# 808_bass_drum1.net
KiCad netlist of a schematic drawn in EAGLE
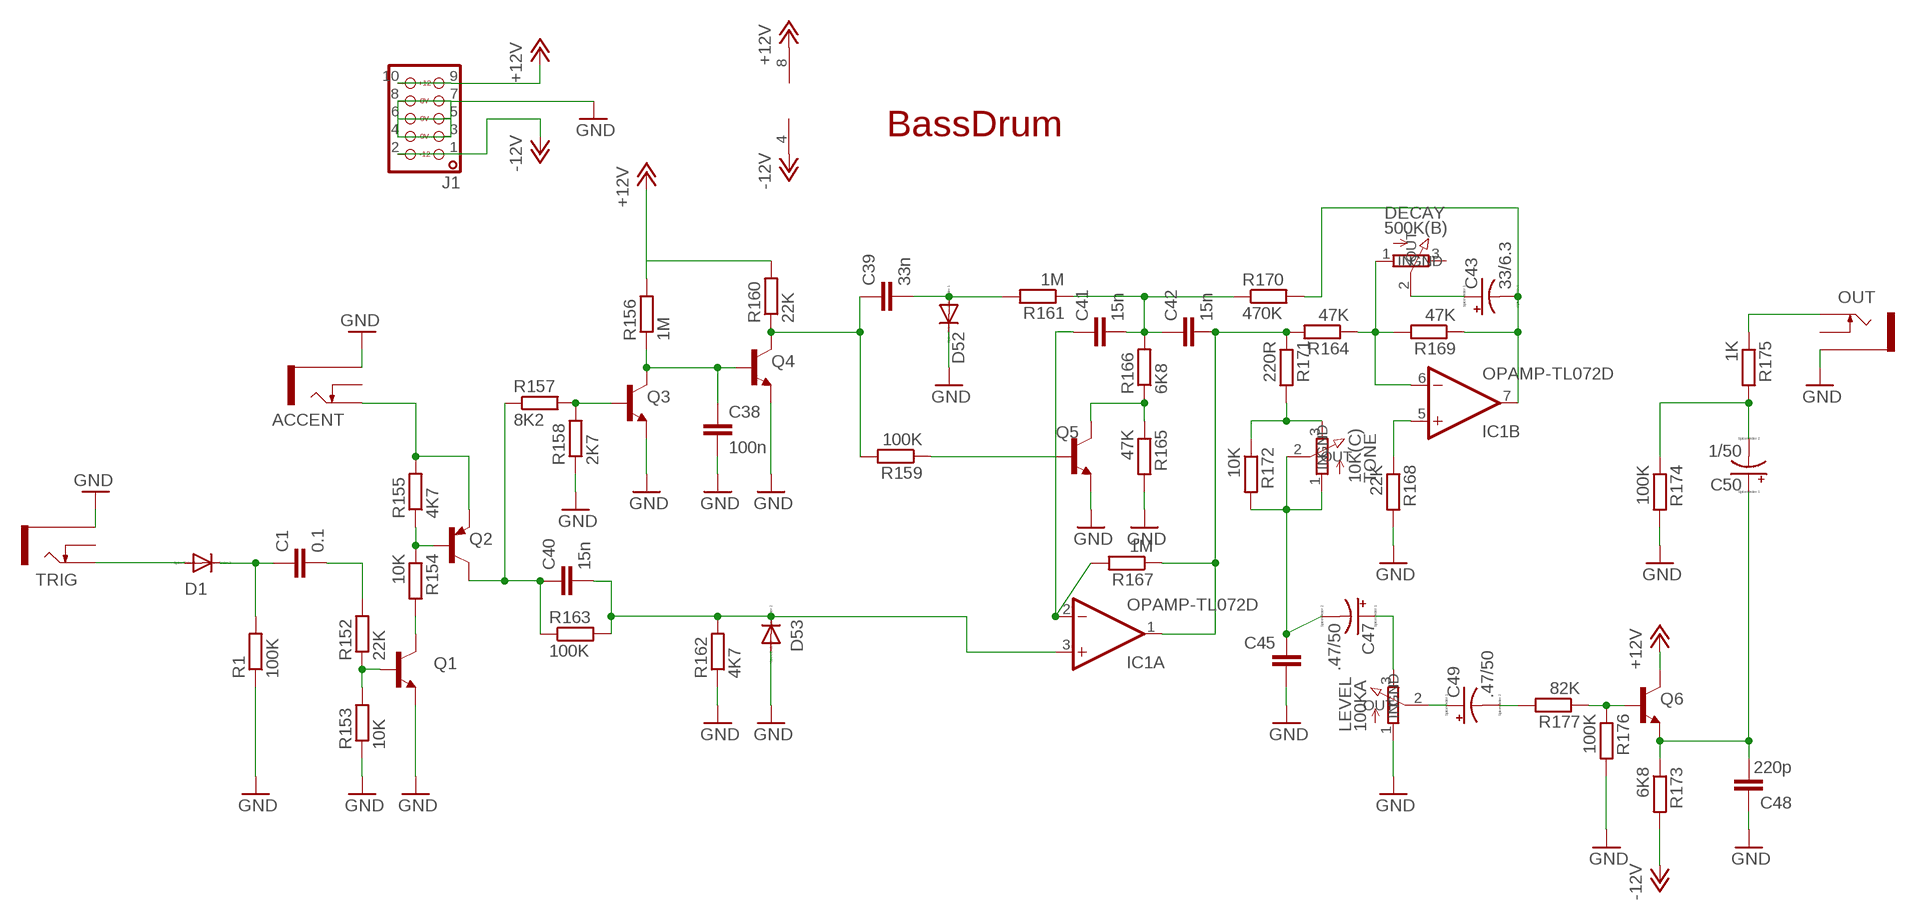
[diagram p0: schematic, sheet 1]

(export (version "E")
  (design (tool "Eeschema 10.0.6"))
  (components
    (comp (ref "ACCENT")
      (value "JACK_THONKICONNNEW")
      (footprint "eagle-import:WQP-PJ301M-12_JACK")
      (libsource (lib "eagle-import") (part "JACK_THONKICONNNEW"))
    )
    (comp (ref "C1")
      (value "0.1")
      (footprint "eagle-import:C0603")
      (libsource (lib "eagle-import") (part "CAPACITOR-EUC0603"))
    )
    (comp (ref "C38")
      (value "100n")
      (footprint "eagle-import:C0603")
      (libsource (lib "eagle-import") (part "CAPACITOR-EUC0603"))
    )
    (comp (ref "C39")
      (value "33n")
      (footprint "eagle-import:C0603")
      (libsource (lib "eagle-import") (part "CAPACITOR-EUC0603"))
    )
    (comp (ref "C40")
      (value "15n")
      (footprint "eagle-import:C0603")
      (libsource (lib "eagle-import") (part "CAPACITOR-EUC0603"))
    )
    (comp (ref "C41")
      (value "15n")
      (footprint "eagle-import:C0603")
      (libsource (lib "eagle-import") (part "CAPACITOR-EUC0603"))
    )
    (comp (ref "C42")
      (value "15n")
      (footprint "eagle-import:C0603")
      (libsource (lib "eagle-import") (part "CAPACITOR-EUC0603"))
    )
    (comp (ref "C43")
      (value "33/6.3")
      (footprint "eagle-import:E2,5-5")
      (libsource (lib "eagle-import") (part "CAPACITOR_POLARIZED-USE2.5-5"))
    )
    (comp (ref "C45")
      (value "100n")
      (footprint "eagle-import:C0603")
      (libsource (lib "eagle-import") (part "CAPACITOR-EUC0603"))
    )
    (comp (ref "C47")
      (value ".47/50")
      (footprint "eagle-import:E2,5-5")
      (libsource (lib "eagle-import") (part "CAPACITOR_POLARIZED-USE2.5-5"))
    )
    (comp (ref "C48")
      (value "220p")
      (footprint "eagle-import:C0603")
      (libsource (lib "eagle-import") (part "CAPACITOR-EUC0603"))
    )
    (comp (ref "C49")
      (value ".47/50")
      (footprint "eagle-import:E2,5-5")
      (libsource (lib "eagle-import") (part "CAPACITOR_POLARIZED-USE2.5-5"))
    )
    (comp (ref "C50")
      (value "1/50")
      (footprint "eagle-import:E2,5-5")
      (libsource (lib "eagle-import") (part "CAPACITOR_POLARIZED-USE2.5-5"))
    )
    (comp (ref "D1")
      (value "1N4148")
      (footprint "eagle-import:SOD323W_INFINEON")
      (libsource (lib "eagle-import") (part "DIODE-1N4148SOD-323"))
    )
    (comp (ref "D52")
      (value "1N4148")
      (footprint "eagle-import:SOD323W_INFINEON")
      (libsource (lib "eagle-import") (part "DIODE-1N4148SOD-323"))
    )
    (comp (ref "D53")
      (value "1N4148")
      (footprint "eagle-import:SOD323W_INFINEON")
      (libsource (lib "eagle-import") (part "DIODE-1N4148SOD-323"))
    )
    (comp (ref "DECAY")
      (value "500K(B)")
      (footprint "eagle-import:9MM_PLS")
      (libsource (lib "eagle-import") (part "POT_9MM_PCB-PLS"))
    )
    (comp (ref "IC1")
      (value "OPAMP-TL072D")
      (footprint "eagle-import:SO08")
      (libsource (lib "eagle-import") (part "OPAMP-TL072D"))
    )
    (comp (ref "J1")
      (value "HEADER-EUROPWR_2X05-OPEN")
      (footprint "eagle-import:2X05_EUROPWR_OPEN")
      (libsource (lib "eagle-import") (part "HEADER-EUROPWR_2X05-OPEN"))
    )
    (comp (ref "LEVEL")
      (value "100KA")
      (footprint "eagle-import:9MM_PLS")
      (libsource (lib "eagle-import") (part "POT_9MM_PCB-PLS"))
    )
    (comp (ref "OUT")
      (value "JACK_THONKICONNNEW")
      (footprint "eagle-import:WQP-PJ301M-12_JACK")
      (libsource (lib "eagle-import") (part "JACK_THONKICONNNEW"))
    )
    (comp (ref "Q1")
      (value "bc546")
      (footprint "eagle-import:SOT23-BEC")
      (libsource (lib "eagle-import") (part "TRANSISTOR-NPN-SOT23-BECBC846ALT1"))
    )
    (comp (ref "Q2")
      (value "bc556")
      (footprint "eagle-import:SOT23-BEC")
      (libsource (lib "eagle-import") (part "TRANSISTOR-PNP-SOT23-BECBC856BLT1"))
    )
    (comp (ref "Q3")
      (value "bc546")
      (footprint "eagle-import:SOT23-BEC")
      (libsource (lib "eagle-import") (part "TRANSISTOR-NPN-SOT23-BECBC846BLT1"))
    )
    (comp (ref "Q4")
      (value "bc546")
      (footprint "eagle-import:SOT23-BEC")
      (libsource (lib "eagle-import") (part "TRANSISTOR-NPN-SOT23-BECBC846BLT1"))
    )
    (comp (ref "Q5")
      (value "bc546")
      (footprint "eagle-import:SOT23-BEC")
      (libsource (lib "eagle-import") (part "TRANSISTOR-NPN-SOT23-BECBC846ALT1"))
    )
    (comp (ref "Q6")
      (value "bc546")
      (footprint "eagle-import:SOT23-BEC")
      (libsource (lib "eagle-import") (part "TRANSISTOR-NPN-SOT23-BECBC846ALT1"))
    )
    (comp (ref "R1")
      (value "100K")
      (footprint "eagle-import:R0603")
      (libsource (lib "eagle-import") (part "RESISTOR-EU_R0603"))
    )
    (comp (ref "R152")
      (value "22K")
      (footprint "eagle-import:R0603")
      (libsource (lib "eagle-import") (part "RESISTOR-EU_R0603"))
    )
    (comp (ref "R153")
      (value "10K")
      (footprint "eagle-import:R0603")
      (libsource (lib "eagle-import") (part "RESISTOR-EU_R0603"))
    )
    (comp (ref "R154")
      (value "10K")
      (footprint "eagle-import:R0603")
      (libsource (lib "eagle-import") (part "RESISTOR-EU_R0603"))
    )
    (comp (ref "R155")
      (value "4K7")
      (footprint "eagle-import:R0603")
      (libsource (lib "eagle-import") (part "RESISTOR-EU_R0603"))
    )
    (comp (ref "R156")
      (value "1M")
      (footprint "eagle-import:R0603")
      (libsource (lib "eagle-import") (part "RESISTOR-EU_R0603"))
    )
    (comp (ref "R157")
      (value "8K2")
      (footprint "eagle-import:R0603")
      (libsource (lib "eagle-import") (part "RESISTOR-EU_R0603"))
    )
    (comp (ref "R158")
      (value "2K7")
      (footprint "eagle-import:R0603")
      (libsource (lib "eagle-import") (part "RESISTOR-EU_R0603"))
    )
    (comp (ref "R159")
      (value "100K")
      (footprint "eagle-import:R0603")
      (libsource (lib "eagle-import") (part "RESISTOR-EU_R0603"))
    )
    (comp (ref "R160")
      (value "22K")
      (footprint "eagle-import:R0603")
      (libsource (lib "eagle-import") (part "RESISTOR-EU_R0603"))
    )
    (comp (ref "R161")
      (value "1M")
      (footprint "eagle-import:R0603")
      (libsource (lib "eagle-import") (part "RESISTOR-EU_R0603"))
    )
    (comp (ref "R162")
      (value "4K7")
      (footprint "eagle-import:R0603")
      (libsource (lib "eagle-import") (part "RESISTOR-EU_R0603"))
    )
    (comp (ref "R163")
      (value "100K")
      (footprint "eagle-import:R0603")
      (libsource (lib "eagle-import") (part "RESISTOR-EU_R0603"))
    )
    (comp (ref "R164")
      (value "47K")
      (footprint "eagle-import:R0603")
      (libsource (lib "eagle-import") (part "RESISTOR-EU_R0603"))
    )
    (comp (ref "R165")
      (value "47K")
      (footprint "eagle-import:R0603")
      (libsource (lib "eagle-import") (part "RESISTOR-EU_R0603"))
    )
    (comp (ref "R166")
      (value "6K8")
      (footprint "eagle-import:R0603")
      (libsource (lib "eagle-import") (part "RESISTOR-EU_R0603"))
    )
    (comp (ref "R167")
      (value "1M")
      (footprint "eagle-import:R0603")
      (libsource (lib "eagle-import") (part "RESISTOR-EU_R0603"))
    )
    (comp (ref "R168")
      (value "22K")
      (footprint "eagle-import:R0603")
      (libsource (lib "eagle-import") (part "RESISTOR-EU_R0603"))
    )
    (comp (ref "R169")
      (value "47K")
      (footprint "eagle-import:R0603")
      (libsource (lib "eagle-import") (part "RESISTOR-EU_R0603"))
    )
    (comp (ref "R170")
      (value "470K")
      (footprint "eagle-import:R0603")
      (libsource (lib "eagle-import") (part "RESISTOR-EU_R0603"))
    )
    (comp (ref "R171")
      (value "220R")
      (footprint "eagle-import:R0603")
      (libsource (lib "eagle-import") (part "RESISTOR-EU_R0603"))
    )
    (comp (ref "R172")
      (value "10K")
      (footprint "eagle-import:R0603")
      (libsource (lib "eagle-import") (part "RESISTOR-EU_R0603"))
    )
    (comp (ref "R173")
      (value "6K8")
      (footprint "eagle-import:R0603")
      (libsource (lib "eagle-import") (part "RESISTOR-EU_R0603"))
    )
    (comp (ref "R174")
      (value "100K")
      (footprint "eagle-import:R0603")
      (libsource (lib "eagle-import") (part "RESISTOR-EU_R0603"))
    )
    (comp (ref "R175")
      (value "1K")
      (footprint "eagle-import:R0603")
      (libsource (lib "eagle-import") (part "RESISTOR-EU_R0603"))
    )
    (comp (ref "R176")
      (value "100K")
      (footprint "eagle-import:R0603")
      (libsource (lib "eagle-import") (part "RESISTOR-EU_R0603"))
    )
    (comp (ref "R177")
      (value "82K")
      (footprint "eagle-import:R0603")
      (libsource (lib "eagle-import") (part "RESISTOR-EU_R0603"))
    )
    (comp (ref "TONE")
      (value "10K(C)")
      (footprint "eagle-import:9MM_PLS")
      (libsource (lib "eagle-import") (part "POT_9MM_PCB-PLS"))
    )
    (comp (ref "TRIG")
      (value "JACK_THONKICONNNEW")
      (footprint "eagle-import:WQP-PJ301M-12_JACK")
      (libsource (lib "eagle-import") (part "JACK_THONKICONNNEW"))
    )
  )
  (nets
    (net (code "1") (name "+12V") (class "Default")
      (node (ref "IC1") (pin "8") (pinfunction "V+_8") (pintype "power_in"))
      (node (ref "J1") (pin "10") (pinfunction "10_10") (pintype "passive"))
      (node (ref "J1") (pin "9") (pinfunction "9_9") (pintype "passive"))
      (node (ref "Q6") (pin "C") (pinfunction "C_C") (pintype "passive"))
      (node (ref "R156") (pin "2") (pinfunction "2_2") (pintype "passive"))
      (node (ref "R160") (pin "2") (pinfunction "2_2") (pintype "passive"))
    )
    (net (code "2") (name "-12V") (class "Default")
      (node (ref "IC1") (pin "4") (pinfunction "V-_4") (pintype "power_in"))
      (node (ref "J1") (pin "1") (pinfunction "1_1") (pintype "passive"))
      (node (ref "J1") (pin "2") (pinfunction "2_2") (pintype "passive"))
      (node (ref "R173") (pin "2") (pinfunction "2_2") (pintype "passive"))
    )
    (net (code "3") (name "GND") (class "Default")
      (node (ref "ACCENT") (pin "P$3_SLEEVE") (pinfunction "SLEEVE_P$3_SLEEVE") (pintype "passive"))
      (node (ref "C38") (pin "2") (pinfunction "2_2") (pintype "passive"))
      (node (ref "C45") (pin "2") (pinfunction "2_2") (pintype "passive"))
      (node (ref "C48") (pin "1") (pinfunction "1_1") (pintype "passive"))
      (node (ref "D52") (pin "C") (pinfunction "C_C") (pintype "passive"))
      (node (ref "D53") (pin "A") (pinfunction "A_A") (pintype "passive"))
      (node (ref "J1") (pin "3") (pinfunction "3_3") (pintype "passive"))
      (node (ref "J1") (pin "4") (pinfunction "4_4") (pintype "passive"))
      (node (ref "J1") (pin "5") (pinfunction "5_5") (pintype "passive"))
      (node (ref "J1") (pin "6") (pinfunction "6_6") (pintype "passive"))
      (node (ref "J1") (pin "7") (pinfunction "7_7") (pintype "passive"))
      (node (ref "J1") (pin "8") (pinfunction "8_8") (pintype "passive"))
      (node (ref "LEVEL") (pin "1") (pinfunction "GND_1") (pintype "passive"))
      (node (ref "OUT") (pin "P$3_SLEEVE") (pinfunction "SLEEVE_P$3_SLEEVE") (pintype "passive"))
      (node (ref "Q1") (pin "E") (pinfunction "E_E") (pintype "passive"))
      (node (ref "Q3") (pin "E") (pinfunction "E_E") (pintype "passive"))
      (node (ref "Q4") (pin "E") (pinfunction "E_E") (pintype "passive"))
      (node (ref "Q5") (pin "E") (pinfunction "E_E") (pintype "passive"))
      (node (ref "R1") (pin "1") (pinfunction "1_1") (pintype "passive"))
      (node (ref "R153") (pin "1") (pinfunction "1_1") (pintype "passive"))
      (node (ref "R158") (pin "1") (pinfunction "1_1") (pintype "passive"))
      (node (ref "R162") (pin "1") (pinfunction "1_1") (pintype "passive"))
      (node (ref "R165") (pin "2") (pinfunction "2_2") (pintype "passive"))
      (node (ref "R168") (pin "2") (pinfunction "2_2") (pintype "passive"))
      (node (ref "R174") (pin "2") (pinfunction "2_2") (pintype "passive"))
      (node (ref "R176") (pin "2") (pinfunction "2_2") (pintype "passive"))
      (node (ref "TRIG") (pin "P$3_SLEEVE") (pinfunction "SLEEVE_P$3_SLEEVE") (pintype "passive"))
    )
    (net (code "4") (name "Net-(ACCENT-TIP)") (class "Default")
      (node (ref "ACCENT") (pin "P$1_TIP") (pinfunction "TIP_P$1_TIP") (pintype "passive"))
      (node (ref "Q2") (pin "E") (pinfunction "E_E") (pintype "passive"))
      (node (ref "R155") (pin "2") (pinfunction "2_2") (pintype "passive"))
    )
    (net (code "5") (name "Net-(C1-Pad1)") (class "Default")
      (node (ref "C1") (pin "1") (pinfunction "1_1") (pintype "passive"))
      (node (ref "D1") (pin "C") (pinfunction "C_C") (pintype "passive"))
      (node (ref "R1") (pin "2") (pinfunction "2_2") (pintype "passive"))
    )
    (net (code "6") (name "Net-(C1-Pad2)") (class "Default")
      (node (ref "C1") (pin "2") (pinfunction "2_2") (pintype "passive"))
      (node (ref "R152") (pin "2") (pinfunction "2_2") (pintype "passive"))
    )
    (net (code "7") (name "Net-(C38-Pad1)") (class "Default")
      (node (ref "C38") (pin "1") (pinfunction "1_1") (pintype "passive"))
      (node (ref "Q3") (pin "C") (pinfunction "C_C") (pintype "passive"))
      (node (ref "Q4") (pin "B") (pinfunction "B_B") (pintype "passive"))
      (node (ref "R156") (pin "1") (pinfunction "1_1") (pintype "passive"))
    )
    (net (code "8") (name "Net-(C39-Pad1)") (class "Default")
      (node (ref "C39") (pin "1") (pinfunction "1_1") (pintype "passive"))
      (node (ref "Q4") (pin "C") (pinfunction "C_C") (pintype "passive"))
      (node (ref "R159") (pin "2") (pinfunction "2_2") (pintype "passive"))
      (node (ref "R160") (pin "1") (pinfunction "1_1") (pintype "passive"))
    )
    (net (code "9") (name "Net-(C39-Pad2)") (class "Default")
      (node (ref "C39") (pin "2") (pinfunction "2_2") (pintype "passive"))
      (node (ref "D52") (pin "A") (pinfunction "A_A") (pintype "passive"))
      (node (ref "R161") (pin "2") (pinfunction "2_2") (pintype "passive"))
    )
    (net (code "10") (name "Net-(C40-Pad1)") (class "Default")
      (node (ref "C40") (pin "1") (pinfunction "1_1") (pintype "passive"))
      (node (ref "Q2") (pin "C") (pinfunction "C_C") (pintype "passive"))
      (node (ref "R157") (pin "1") (pinfunction "1_1") (pintype "passive"))
      (node (ref "R163") (pin "1") (pinfunction "1_1") (pintype "passive"))
    )
    (net (code "11") (name "Net-(C41-Pad2)") (class "Default")
      (node (ref "C41") (pin "2") (pinfunction "2_2") (pintype "passive"))
      (node (ref "C42") (pin "1") (pinfunction "1_1") (pintype "passive"))
      (node (ref "R161") (pin "1") (pinfunction "1_1") (pintype "passive"))
      (node (ref "R166") (pin "2") (pinfunction "2_2") (pintype "passive"))
      (node (ref "R170") (pin "1") (pinfunction "1_1") (pintype "passive"))
    )
    (net (code "12") (name "Net-(C48-Pad2)") (class "Default")
      (node (ref "C48") (pin "2") (pinfunction "2_2") (pintype "passive"))
      (node (ref "C50") (pin "+") (pinfunction "+_+") (pintype "passive"))
      (node (ref "Q6") (pin "E") (pinfunction "E_E") (pintype "passive"))
      (node (ref "R173") (pin "1") (pinfunction "1_1") (pintype "passive"))
    )
    (net (code "13") (name "Net-(C49-Pad-)") (class "Default")
      (node (ref "C49") (pin "-") (pinfunction "-_-") (pintype "passive"))
      (node (ref "R177") (pin "2") (pinfunction "2_2") (pintype "passive"))
    )
    (net (code "14") (name "Net-(C50-Pad-)") (class "Default")
      (node (ref "C50") (pin "-") (pinfunction "-_-") (pintype "passive"))
      (node (ref "R174") (pin "1") (pinfunction "1_1") (pintype "passive"))
      (node (ref "R175") (pin "2") (pinfunction "2_2") (pintype "passive"))
    )
    (net (code "15") (name "Net-(DECAY-GND)") (class "Default")
      (node (ref "DECAY") (pin "1") (pinfunction "GND_1") (pintype "passive"))
      (node (ref "IC1") (pin "6") (pinfunction "-IN_6") (pintype "input"))
      (node (ref "R164") (pin "1") (pinfunction "1_1") (pintype "passive"))
      (node (ref "R169") (pin "2") (pinfunction "2_2") (pintype "passive"))
    )
    (net (code "16") (name "Net-(DECAY-OUT)") (class "Default")
      (node (ref "C43") (pin "+") (pinfunction "+_+") (pintype "passive"))
      (node (ref "DECAY") (pin "2") (pinfunction "OUT_2") (pintype "passive"))
    )
    (net (code "17") (name "Net-(IC1A-+IN)") (class "Default")
      (node (ref "C40") (pin "2") (pinfunction "2_2") (pintype "passive"))
      (node (ref "D53") (pin "C") (pinfunction "C_C") (pintype "passive"))
      (node (ref "IC1") (pin "3") (pinfunction "+IN_3") (pintype "input"))
      (node (ref "R162") (pin "2") (pinfunction "2_2") (pintype "passive"))
      (node (ref "R163") (pin "2") (pinfunction "2_2") (pintype "passive"))
    )
    (net (code "18") (name "Net-(IC1A--IN)") (class "Default")
      (node (ref "C41") (pin "1") (pinfunction "1_1") (pintype "passive"))
      (node (ref "IC1") (pin "2") (pinfunction "-IN_2") (pintype "input"))
      (node (ref "R167") (pin "2") (pinfunction "2_2") (pintype "passive"))
    )
    (net (code "19") (name "Net-(IC1A-OUT)") (class "Default")
      (node (ref "C42") (pin "2") (pinfunction "2_2") (pintype "passive"))
      (node (ref "IC1") (pin "1") (pinfunction "OUT_1") (pintype "output"))
      (node (ref "R164") (pin "2") (pinfunction "2_2") (pintype "passive"))
      (node (ref "R167") (pin "1") (pinfunction "1_1") (pintype "passive"))
      (node (ref "R171") (pin "1") (pinfunction "1_1") (pintype "passive"))
    )
    (net (code "20") (name "Net-(IC1B-+IN)") (class "Default")
      (node (ref "IC1") (pin "5") (pinfunction "+IN_5") (pintype "input"))
      (node (ref "R168") (pin "1") (pinfunction "1_1") (pintype "passive"))
    )
    (net (code "21") (name "Net-(IC1B-OUT)") (class "Default")
      (node (ref "C43") (pin "-") (pinfunction "-_-") (pintype "passive"))
      (node (ref "IC1") (pin "7") (pinfunction "OUT_7") (pintype "output"))
      (node (ref "R169") (pin "1") (pinfunction "1_1") (pintype "passive"))
      (node (ref "R170") (pin "2") (pinfunction "2_2") (pintype "passive"))
    )
    (net (code "22") (name "Net-(LEVEL-IN)") (class "Default")
      (node (ref "C47") (pin "+") (pinfunction "+_+") (pintype "passive"))
      (node (ref "LEVEL") (pin "3") (pinfunction "IN_3") (pintype "passive"))
    )
    (net (code "23") (name "Net-(LEVEL-OUT)") (class "Default")
      (node (ref "C49") (pin "+") (pinfunction "+_+") (pintype "passive"))
      (node (ref "LEVEL") (pin "2") (pinfunction "OUT_2") (pintype "passive"))
    )
    (net (code "24") (name "Net-(OUT-TIP)") (class "Default")
      (node (ref "OUT") (pin "P$1_TIP") (pinfunction "TIP_P$1_TIP") (pintype "passive"))
      (node (ref "R175") (pin "1") (pinfunction "1_1") (pintype "passive"))
    )
    (net (code "25") (name "Net-(Q1-PadB)") (class "Default")
      (node (ref "Q1") (pin "B") (pinfunction "B_B") (pintype "passive"))
      (node (ref "R152") (pin "1") (pinfunction "1_1") (pintype "passive"))
      (node (ref "R153") (pin "2") (pinfunction "2_2") (pintype "passive"))
    )
    (net (code "26") (name "Net-(Q1-PadC)") (class "Default")
      (node (ref "Q1") (pin "C") (pinfunction "C_C") (pintype "passive"))
      (node (ref "R154") (pin "2") (pinfunction "2_2") (pintype "passive"))
    )
    (net (code "27") (name "Net-(Q2-PadB)") (class "Default")
      (node (ref "Q2") (pin "B") (pinfunction "B_B") (pintype "passive"))
      (node (ref "R154") (pin "1") (pinfunction "1_1") (pintype "passive"))
      (node (ref "R155") (pin "1") (pinfunction "1_1") (pintype "passive"))
    )
    (net (code "28") (name "Net-(Q3-PadB)") (class "Default")
      (node (ref "Q3") (pin "B") (pinfunction "B_B") (pintype "passive"))
      (node (ref "R157") (pin "2") (pinfunction "2_2") (pintype "passive"))
      (node (ref "R158") (pin "2") (pinfunction "2_2") (pintype "passive"))
    )
    (net (code "29") (name "Net-(Q5-PadB)") (class "Default")
      (node (ref "Q5") (pin "B") (pinfunction "B_B") (pintype "passive"))
      (node (ref "R159") (pin "1") (pinfunction "1_1") (pintype "passive"))
    )
    (net (code "30") (name "Net-(Q5-PadC)") (class "Default")
      (node (ref "Q5") (pin "C") (pinfunction "C_C") (pintype "passive"))
      (node (ref "R165") (pin "1") (pinfunction "1_1") (pintype "passive"))
      (node (ref "R166") (pin "1") (pinfunction "1_1") (pintype "passive"))
    )
    (net (code "31") (name "Net-(Q6-PadB)") (class "Default")
      (node (ref "Q6") (pin "B") (pinfunction "B_B") (pintype "passive"))
      (node (ref "R176") (pin "1") (pinfunction "1_1") (pintype "passive"))
      (node (ref "R177") (pin "1") (pinfunction "1_1") (pintype "passive"))
    )
    (net (code "32") (name "Net-(TONE-GND)") (class "Default")
      (node (ref "C45") (pin "1") (pinfunction "1_1") (pintype "passive"))
      (node (ref "C47") (pin "-") (pinfunction "-_-") (pintype "passive"))
      (node (ref "R172") (pin "2") (pinfunction "2_2") (pintype "passive"))
      (node (ref "TONE") (pin "1") (pinfunction "GND_1") (pintype "passive"))
      (node (ref "TONE") (pin "2") (pinfunction "OUT_2") (pintype "passive"))
    )
    (net (code "33") (name "Net-(TONE-IN)") (class "Default")
      (node (ref "R171") (pin "2") (pinfunction "2_2") (pintype "passive"))
      (node (ref "R172") (pin "1") (pinfunction "1_1") (pintype "passive"))
      (node (ref "TONE") (pin "3") (pinfunction "IN_3") (pintype "passive"))
    )
    (net (code "34") (name "Net-(TRIG-TIP)") (class "Default")
      (node (ref "D1") (pin "A") (pinfunction "A_A") (pintype "passive"))
      (node (ref "TRIG") (pin "P$1_TIP") (pinfunction "TIP_P$1_TIP") (pintype "passive"))
    )
    (net (code "35") (name "unconnected-(ACCENT-SWITCH-PadP$2_SWITCH)") (class "Default")
      (node (ref "ACCENT") (pin "P$2_SWITCH") (pinfunction "SWITCH_P$2_SWITCH") (pintype "passive"))
    )
    (net (code "36") (name "unconnected-(DECAY-IN-Pad3)") (class "Default")
      (node (ref "DECAY") (pin "3") (pinfunction "IN_3") (pintype "passive"))
    )
    (net (code "37") (name "unconnected-(OUT-SWITCH-PadP$2_SWITCH)") (class "Default")
      (node (ref "OUT") (pin "P$2_SWITCH") (pinfunction "SWITCH_P$2_SWITCH") (pintype "passive"))
    )
    (net (code "38") (name "unconnected-(TRIG-SWITCH-PadP$2_SWITCH)") (class "Default")
      (node (ref "TRIG") (pin "P$2_SWITCH") (pinfunction "SWITCH_P$2_SWITCH") (pintype "passive"))
    )
  )
)
